# A6C.net
KiCad netlist of a schematic drawn in Altium Designer
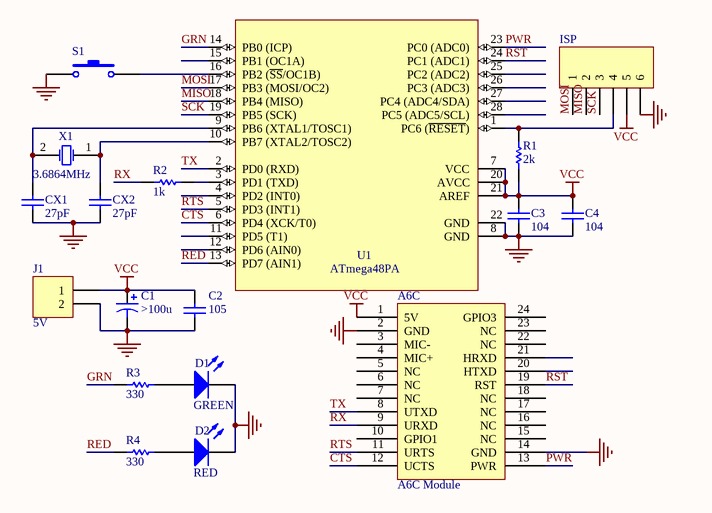
[diagram p0: A6C.SchDoc]

(export (version "E")
  (design (tool "Eeschema 10.0.6"))
  (components
    (comp (ref "A6C") (value "A6C Module") (libsource (lib "A6C") (part "Component_1")))
    (comp (ref "C1")
      (value ">100u")
      (description "Polarized Capacitor (Radial)")
      (fields (field (name "PUBLISHER") "Altium Limited"))
      (libsource (lib "Miscellaneous Devices") (part "Cap Pol1"))
    )
    (comp (ref "C2")
      (value "105")
      (footprint "RAD-0.1nar")
      (description "Capacitor")
      (fields (field (name "PUBLISHER") "Altium Limited"))
      (libsource (lib "Miscellaneous Devices") (part "Cap"))
    )
    (comp (ref "C3")
      (value "104")
      (description "Capacitor")
      (fields (field (name "PUBLISHER") "Altium Limited"))
      (libsource (lib "Miscellaneous Devices") (part "Cap"))
    )
    (comp (ref "C4")
      (value "104")
      (description "Capacitor")
      (fields (field (name "PUBLISHER") "Altium Limited"))
      (libsource (lib "Miscellaneous Devices") (part "Cap"))
    )
    (comp (ref "CX1")
      (value "27pF")
      (description "Capacitor")
      (fields (field (name "PUBLISHER") "Altium Limited"))
      (libsource (lib "Miscellaneous Devices") (part "Cap"))
    )
    (comp (ref "CX2")
      (value "27pF")
      (description "Capacitor")
      (fields (field (name "PUBLISHER") "Altium Limited"))
      (libsource (lib "Miscellaneous Devices") (part "Cap"))
    )
    (comp (ref "D1")
      (value "GREEN")
      (footprint "LED-0")
      (description "Typical INFRARED GaAs LED")
      (fields (field (name "PUBLISHER") "Altium Limited"))
      (libsource (lib "Miscellaneous Devices") (part "LED0"))
    )
    (comp (ref "D2")
      (value "RED")
      (footprint "LED-0")
      (description "Typical INFRARED GaAs LED")
      (fields (field (name "PUBLISHER") "Altium Limited"))
      (libsource (lib "Miscellaneous Devices") (part "LED0"))
    )
    (comp (ref "ISP")
      (value "ISP")
      (footprint "PHOeNIX6")
      (description "Header, 6-Pin")
      (fields (field (name "PUBLISHER") "Altium Limited"))
      (libsource (lib "Miscellaneous Connectors") (part "Header 6"))
    )
    (comp (ref "J1")
      (value "5V")
      (footprint "Phoenix2")
      (description "Header, 2-Pin")
      (fields (field (name "PUBLISHER") "Altium Limited"))
      (libsource (lib "Mylib2.5") (part "Header 2"))
    )
    (comp (ref "R1")
      (value "2k")
      (description "Semiconductor Resistor")
      (fields (field (name "PUBLISHER") "Altium Limited"))
      (libsource (lib "Miscellaneous Devices") (part "Res Semi"))
    )
    (comp (ref "R2")
      (value "1k")
      (description "Semiconductor Resistor")
      (fields (field (name "PUBLISHER") "Altium Limited"))
      (libsource (lib "Miscellaneous Devices") (part "Res Semi"))
    )
    (comp (ref "R3")
      (value "330")
      (description "Semiconductor Resistor")
      (fields (field (name "PUBLISHER") "Altium Limited"))
      (libsource (lib "Miscellaneous Devices") (part "Res Semi"))
    )
    (comp (ref "R4")
      (value "330")
      (description "Semiconductor Resistor")
      (fields (field (name "PUBLISHER") "Altium Limited"))
      (libsource (lib "Miscellaneous Devices") (part "Res Semi"))
    )
    (comp (ref "S1")
      (value "SW-PB")
      (footprint "SPST-2")
      (description "Switch")
      (fields (field (name "PUBLISHER") "Altium Limited"))
      (libsource (lib "Miscellaneous Devices") (part "SW-PB"))
    )
    (comp (ref "U1")
      (value "ATmega48PA")
      (footprint "My_28P3")
      (description "AVR 8K Bytes of In-System Programmable Flash Memory")
      (fields (field (name "PUBLISHER") "Altium Limited"))
      (libsource (lib "Mylib1.5") (part "ATmega8-16PI"))
    )
    (comp (ref "X1")
      (value "3.6864MHz")
      (footprint "XTAL_1")
      (description "Crystal Oscillator")
      (fields (field (name "PUBLISHER") "Altium Limited"))
      (libsource (lib "Miscellaneous Devices") (part "XTAL"))
    )
  )
  (nets
    (net (code "1") (name "/CTS") (class "Default")
      (node (ref "A6C") (pin "12") (pinfunction "UCTS_12") (pintype "passive"))
      (node (ref "U1") (pin "6") (pinfunction "PD4_(XCK/T0)_6") (pintype "bidirectional"))
    )
    (net (code "2") (name "/GRN") (class "Default")
      (node (ref "R3") (pin "1") (pinfunction "1_1") (pintype "passive"))
      (node (ref "U1") (pin "14") (pinfunction "PB0_(ICP)_14") (pintype "bidirectional"))
    )
    (net (code "3") (name "/MISO") (class "Default")
      (node (ref "ISP") (pin "2") (pinfunction "2_2") (pintype "passive"))
      (node (ref "U1") (pin "18") (pinfunction "PB4_(MISO)_18") (pintype "bidirectional"))
    )
    (net (code "4") (name "/MOSI") (class "Default")
      (node (ref "ISP") (pin "1") (pinfunction "1_1") (pintype "passive"))
      (node (ref "U1") (pin "17") (pinfunction "PB3_(MOSI/OC2)_17") (pintype "bidirectional"))
    )
    (net (code "5") (name "/PWR") (class "Default")
      (node (ref "A6C") (pin "13") (pinfunction "PWR_13") (pintype "passive"))
      (node (ref "U1") (pin "23") (pinfunction "PC0_(ADC0)_23") (pintype "bidirectional"))
    )
    (net (code "6") (name "/RED") (class "Default")
      (node (ref "R4") (pin "1") (pinfunction "1_1") (pintype "passive"))
      (node (ref "U1") (pin "13") (pinfunction "PD7_(AIN1)_13") (pintype "bidirectional"))
    )
    (net (code "7") (name "/RST") (class "Default")
      (node (ref "A6C") (pin "19") (pinfunction "RST_19") (pintype "power_in"))
      (node (ref "U1") (pin "24") (pinfunction "PC1_(ADC1)_24") (pintype "bidirectional"))
    )
    (net (code "8") (name "/RTS") (class "Default")
      (node (ref "A6C") (pin "11") (pinfunction "URTS_11") (pintype "passive"))
      (node (ref "U1") (pin "5") (pinfunction "PD3_(INT1)_5") (pintype "bidirectional"))
    )
    (net (code "9") (name "/RX") (class "Default")
      (node (ref "A6C") (pin "9") (pinfunction "URXD_9") (pintype "passive"))
      (node (ref "R2") (pin "1") (pinfunction "1_1") (pintype "passive"))
    )
    (net (code "10") (name "/SCK") (class "Default")
      (node (ref "ISP") (pin "3") (pinfunction "3_3") (pintype "passive"))
      (node (ref "U1") (pin "19") (pinfunction "PB5_(SCK)_19") (pintype "bidirectional"))
    )
    (net (code "11") (name "/TX") (class "Default")
      (node (ref "A6C") (pin "8") (pinfunction "UTXD_8") (pintype "passive"))
      (node (ref "U1") (pin "2") (pinfunction "PD0_(RXD)_2") (pintype "bidirectional"))
    )
    (net (code "12") (name "GND") (class "Default")
      (node (ref "A6C") (pin "14") (pinfunction "GND_14") (pintype "power_in"))
      (node (ref "A6C") (pin "2") (pinfunction "GND_2") (pintype "power_in"))
      (node (ref "C1") (pin "2") (pinfunction "2_2") (pintype "passive"))
      (node (ref "C2") (pin "1") (pinfunction "1_1") (pintype "passive"))
      (node (ref "C3") (pin "2") (pinfunction "2_2") (pintype "passive"))
      (node (ref "C4") (pin "2") (pinfunction "2_2") (pintype "passive"))
      (node (ref "CX1") (pin "2") (pinfunction "2_2") (pintype "passive"))
      (node (ref "CX2") (pin "2") (pinfunction "2_2") (pintype "passive"))
      (node (ref "D1") (pin "2") (pinfunction "K_2") (pintype "passive"))
      (node (ref "D2") (pin "2") (pinfunction "K_2") (pintype "passive"))
      (node (ref "ISP") (pin "6") (pinfunction "6_6") (pintype "passive"))
      (node (ref "J1") (pin "2") (pinfunction "2_2") (pintype "passive"))
      (node (ref "S1") (pin "1") (pinfunction "1_1") (pintype "passive"))
      (node (ref "U1") (pin "22") (pinfunction "GND_22") (pintype "power_in"))
      (node (ref "U1") (pin "8") (pinfunction "GND_8") (pintype "power_in"))
    )
    (net (code "13") (name "Net-(D1-A)") (class "Default")
      (node (ref "D1") (pin "1") (pinfunction "A_1") (pintype "passive"))
      (node (ref "R3") (pin "2") (pinfunction "2_2") (pintype "passive"))
    )
    (net (code "14") (name "Net-(D2-A)") (class "Default")
      (node (ref "D2") (pin "1") (pinfunction "A_1") (pintype "passive"))
      (node (ref "R4") (pin "2") (pinfunction "2_2") (pintype "passive"))
    )
    (net (code "15") (name "Net-(U1-PB2_(~{SS}{slash}OC1B))") (class "Default")
      (node (ref "S1") (pin "2") (pinfunction "2_2") (pintype "passive"))
      (node (ref "U1") (pin "16") (pinfunction "PB2_(~{SS}/OC1B)_16") (pintype "bidirectional"))
    )
    (net (code "16") (name "Net-(U1-PB6_(XTAL1{slash}TOSC1))") (class "Default")
      (node (ref "CX1") (pin "1") (pinfunction "1_1") (pintype "passive"))
      (node (ref "U1") (pin "9") (pinfunction "PB6_(XTAL1/TOSC1)_9") (pintype "bidirectional"))
      (node (ref "X1") (pin "2") (pinfunction "OSC2_2") (pintype "passive"))
    )
    (net (code "17") (name "Net-(U1-PB7_(XTAL2{slash}TOSC2))") (class "Default")
      (node (ref "CX2") (pin "1") (pinfunction "1_1") (pintype "passive"))
      (node (ref "U1") (pin "10") (pinfunction "PB7_(XTAL2/TOSC2)_10") (pintype "bidirectional"))
      (node (ref "X1") (pin "1") (pinfunction "OSC1_1") (pintype "passive"))
    )
    (net (code "18") (name "Net-(U1-PC6_(~{RESET}))") (class "Default")
      (node (ref "ISP") (pin "4") (pinfunction "4_4") (pintype "passive"))
      (node (ref "R1") (pin "1") (pinfunction "1_1") (pintype "passive"))
      (node (ref "U1") (pin "1") (pinfunction "PC6_(~{RESET})_1") (pintype "bidirectional"))
    )
    (net (code "19") (name "Net-(U1-PD1_(TXD))") (class "Default")
      (node (ref "R2") (pin "2") (pinfunction "2_2") (pintype "passive"))
      (node (ref "U1") (pin "3") (pinfunction "PD1_(TXD)_3") (pintype "bidirectional"))
    )
    (net (code "20") (name "VCC") (class "Default")
      (node (ref "A6C") (pin "1") (pinfunction "5V_1") (pintype "power_in"))
      (node (ref "C1") (pin "1") (pinfunction "1_1") (pintype "passive"))
      (node (ref "C2") (pin "2") (pinfunction "2_2") (pintype "passive"))
      (node (ref "C3") (pin "1") (pinfunction "1_1") (pintype "passive"))
      (node (ref "C4") (pin "1") (pinfunction "1_1") (pintype "passive"))
      (node (ref "ISP") (pin "5") (pinfunction "5_5") (pintype "passive"))
      (node (ref "J1") (pin "1") (pinfunction "1_1") (pintype "passive"))
      (node (ref "R1") (pin "2") (pinfunction "2_2") (pintype "passive"))
      (node (ref "U1") (pin "20") (pinfunction "AVCC_20") (pintype "power_in"))
      (node (ref "U1") (pin "21") (pinfunction "AREF_21") (pintype "passive"))
      (node (ref "U1") (pin "7") (pinfunction "VCC_7") (pintype "power_in"))
    )
    (net (code "21") (name "unconnected-(A6C-GPIO1-Pad10)") (class "Default")
      (node (ref "A6C") (pin "10") (pinfunction "GPIO1_10") (pintype "passive"))
    )
    (net (code "22") (name "unconnected-(A6C-GPIO3-Pad24)") (class "Default")
      (node (ref "A6C") (pin "24") (pinfunction "GPIO3_24") (pintype "passive"))
    )
    (net (code "23") (name "unconnected-(A6C-HRXD-Pad21)") (class "Default")
      (node (ref "A6C") (pin "21") (pinfunction "HRXD_21") (pintype "passive"))
    )
    (net (code "24") (name "unconnected-(A6C-HTXD-Pad20)") (class "Default")
      (node (ref "A6C") (pin "20") (pinfunction "HTXD_20") (pintype "passive"))
    )
    (net (code "25") (name "unconnected-(A6C-MIC+-Pad4)") (class "Default")
      (node (ref "A6C") (pin "4") (pinfunction "MIC+_4") (pintype "passive"))
    )
    (net (code "26") (name "unconnected-(A6C-MIC--Pad3)") (class "Default")
      (node (ref "A6C") (pin "3") (pinfunction "MIC-_3") (pintype "passive"))
    )
    (net (code "27") (name "unconnected-(A6C-NC-Pad5)") (class "Default")
      (node (ref "A6C") (pin "5") (pinfunction "NC_5") (pintype "passive"))
    )
    (net (code "28") (name "unconnected-(A6C-NC-Pad6)") (class "Default")
      (node (ref "A6C") (pin "6") (pinfunction "NC_6") (pintype "passive"))
    )
    (net (code "29") (name "unconnected-(A6C-NC-Pad7)") (class "Default")
      (node (ref "A6C") (pin "7") (pinfunction "NC_7") (pintype "passive"))
    )
    (net (code "30") (name "unconnected-(A6C-NC-Pad15)") (class "Default")
      (node (ref "A6C") (pin "15") (pinfunction "NC_15") (pintype "passive"))
    )
    (net (code "31") (name "unconnected-(A6C-NC-Pad16)") (class "Default")
      (node (ref "A6C") (pin "16") (pinfunction "NC_16") (pintype "passive"))
    )
    (net (code "32") (name "unconnected-(A6C-NC-Pad17)") (class "Default")
      (node (ref "A6C") (pin "17") (pinfunction "NC_17") (pintype "passive"))
    )
    (net (code "33") (name "unconnected-(A6C-NC-Pad18)") (class "Default")
      (node (ref "A6C") (pin "18") (pinfunction "NC_18") (pintype "passive"))
    )
    (net (code "34") (name "unconnected-(A6C-NC-Pad22)") (class "Default")
      (node (ref "A6C") (pin "22") (pinfunction "NC_22") (pintype "passive"))
    )
    (net (code "35") (name "unconnected-(A6C-NC-Pad23)") (class "Default")
      (node (ref "A6C") (pin "23") (pinfunction "NC_23") (pintype "passive"))
    )
    (net (code "36") (name "unconnected-(U1-PB1_(OC1A)-Pad15)") (class "Default")
      (node (ref "U1") (pin "15") (pinfunction "PB1_(OC1A)_15") (pintype "bidirectional"))
    )
    (net (code "37") (name "unconnected-(U1-PC2_(ADC2)-Pad25)") (class "Default")
      (node (ref "U1") (pin "25") (pinfunction "PC2_(ADC2)_25") (pintype "bidirectional"))
    )
    (net (code "38") (name "unconnected-(U1-PC3_(ADC3)-Pad26)") (class "Default")
      (node (ref "U1") (pin "26") (pinfunction "PC3_(ADC3)_26") (pintype "bidirectional"))
    )
    (net (code "39") (name "unconnected-(U1-PC4_(ADC4{slash}SDA)-Pad27)") (class "Default")
      (node (ref "U1") (pin "27") (pinfunction "PC4_(ADC4/SDA)_27") (pintype "bidirectional"))
    )
    (net (code "40") (name "unconnected-(U1-PC5_(ADC5{slash}SCL)-Pad28)") (class "Default")
      (node (ref "U1") (pin "28") (pinfunction "PC5_(ADC5/SCL)_28") (pintype "bidirectional"))
    )
    (net (code "41") (name "unconnected-(U1-PD2_(INT0)-Pad4)") (class "Default")
      (node (ref "U1") (pin "4") (pinfunction "PD2_(INT0)_4") (pintype "bidirectional"))
    )
    (net (code "42") (name "unconnected-(U1-PD5_(T1)-Pad11)") (class "Default")
      (node (ref "U1") (pin "11") (pinfunction "PD5_(T1)_11") (pintype "bidirectional"))
    )
    (net (code "43") (name "unconnected-(U1-PD6_(AIN0)-Pad12)") (class "Default")
      (node (ref "U1") (pin "12") (pinfunction "PD6_(AIN0)_12") (pintype "bidirectional"))
    )
  )
)
